# LoRaNow_v0.net
KiCad netlist of a schematic drawn in EAGLE
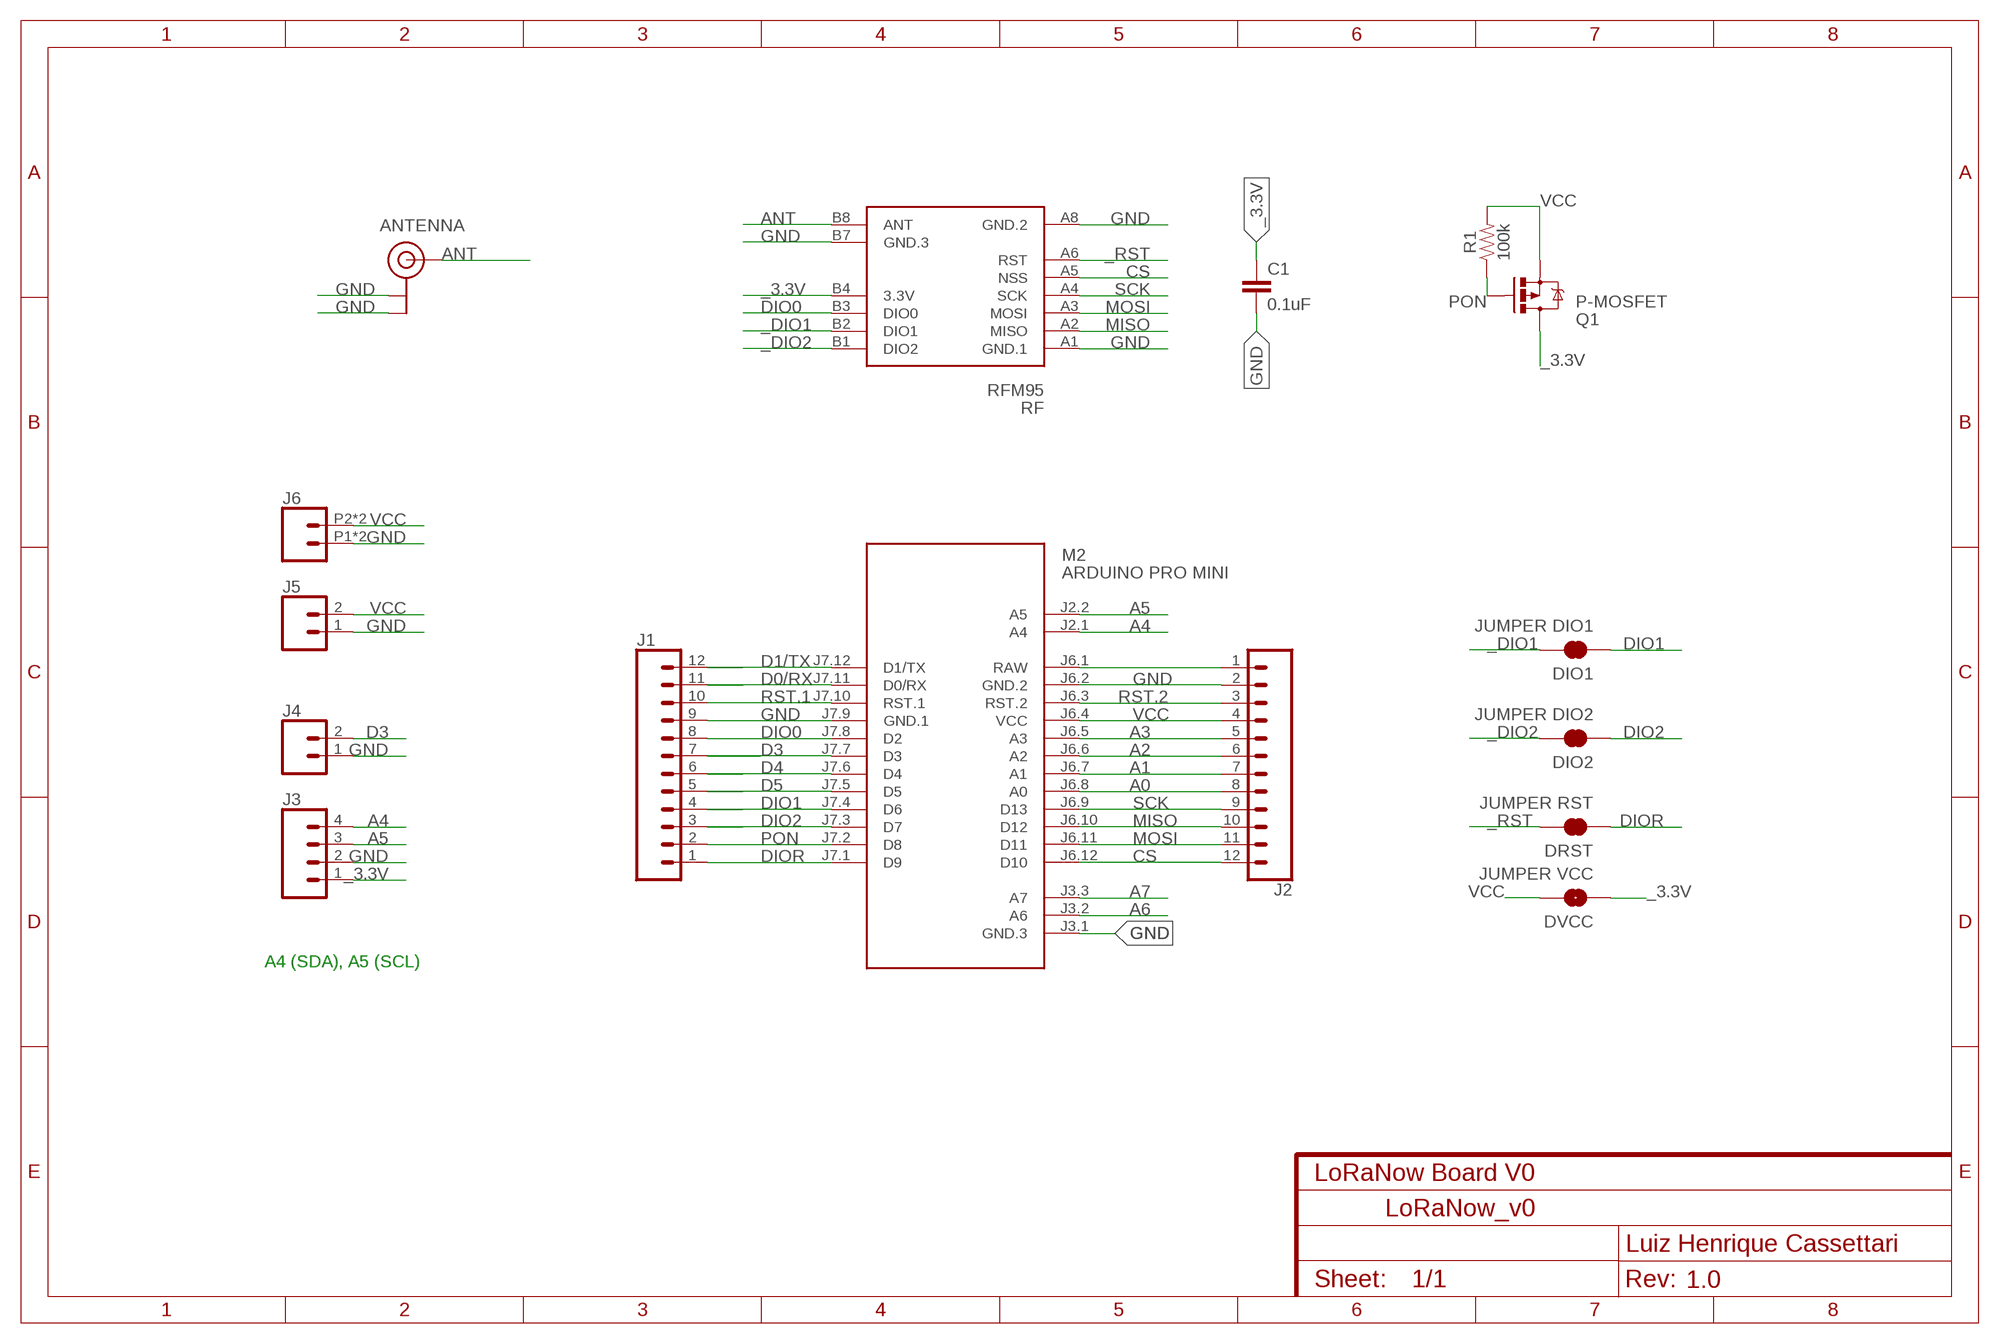
[diagram p0: schematic, sheet 1]

(export (version "E")
  (design (tool "Eeschema 10.0.6"))
  (components
    (comp (ref "ANTENNA")
      (value "U.FLU.FL2")
      (footprint "eagle-import:U.FL_2")
      (libsource (lib "eagle-import") (part "U.FLU.FL2"))
    )
    (comp (ref "C1")
      (value "0.1uF")
      (footprint "eagle-import:C0603K")
      (libsource (lib "eagle-import") (part "C-EUC0603K"))
    )
    (comp (ref "DIO1")
      (value "JUMPER DIO1")
      (footprint "eagle-import:SMT-JUMPER_2_NC_TRACE_NO-SILK")
      (libsource (lib "eagle-import") (part "JUMPER-SMT_2_NC_TRACE_NO-SILK"))
    )
    (comp (ref "DIO2")
      (value "JUMPER DIO2")
      (footprint "eagle-import:SMT-JUMPER_2_NC_TRACE_NO-SILK")
      (libsource (lib "eagle-import") (part "JUMPER-SMT_2_NC_TRACE_NO-SILK"))
    )
    (comp (ref "DRST")
      (value "JUMPER RST")
      (footprint "eagle-import:SMT-JUMPER_2_NC_TRACE_NO-SILK")
      (libsource (lib "eagle-import") (part "JUMPER-SMT_2_NC_TRACE_NO-SILK"))
    )
    (comp (ref "DVCC")
      (value "JUMPER VCC")
      (footprint "eagle-import:SMT-JUMPER_2_NO_NO-SILK")
      (libsource (lib "eagle-import") (part "JUMPER-SMT_2_NO_NO-SILK"))
    )
    (comp (ref "J1")
      (value "CONN_12NO_SILK")
      (footprint "eagle-import:1X12_NO_SILK")
      (libsource (lib "eagle-import") (part "CONN_12NO_SILK"))
    )
    (comp (ref "J2")
      (value "CONN_12NO_SILK")
      (footprint "eagle-import:1X12_NO_SILK")
      (libsource (lib "eagle-import") (part "CONN_12NO_SILK"))
    )
    (comp (ref "J3")
      (value "CONN_041X04_NO_SILK")
      (footprint "eagle-import:1X04_NO_SILK")
      (libsource (lib "eagle-import") (part "CONN_041X04_NO_SILK"))
    )
    (comp (ref "J4")
      (value "CONN_021X02_NO_SILK")
      (footprint "eagle-import:1X02_NO_SILK")
      (libsource (lib "eagle-import") (part "CONN_021X02_NO_SILK"))
    )
    (comp (ref "J5")
      (value "CONN_021X02_NO_SILK")
      (footprint "eagle-import:1X02_NO_SILK")
      (libsource (lib "eagle-import") (part "CONN_021X02_NO_SILK"))
    )
    (comp (ref "J6")
      (value "CONN_02SMALL_POKEHOME")
      (footprint "eagle-import:1X02_POKEHOME")
      (libsource (lib "eagle-import") (part "CONN_02SMALL_POKEHOME"))
    )
    (comp (ref "M2")
      (value "ARDUINO PRO MINI")
      (footprint "eagle-import:ARDUINO-PRO-MINI#NP#2")
      (libsource (lib "eagle-import") (part "ARDUINO-PRO-MINI-#NP2"))
    )
    (comp (ref "Q1")
      (value "P-MOSFET")
      (footprint "eagle-import:SOT23-3")
      (libsource (lib "eagle-import") (part "MOSFET-PCHANNELSMD"))
    )
    (comp (ref "R1")
      (value "100k")
      (footprint "eagle-import:0603")
      (libsource (lib "eagle-import") (part "100KOHM-0603-1/10W-1%"))
    )
    (comp (ref "RF")
      (value "RFM95")
      (footprint "eagle-import:WIRELESS-LORA-RFM95W#SMD#2")
      (libsource (lib "eagle-import") (part "WIRELESS-LORA-RFM95W-LORANOW"))
    )
  )
  (nets
    (net (code "1") (name "/A0") (class "Default")
      (node (ref "J2") (pin "8") (pinfunction "8_8") (pintype "passive"))
      (node (ref "M2") (pin "J6.8") (pinfunction "A0_J6.8") (pintype "bidirectional"))
    )
    (net (code "2") (name "/A1") (class "Default")
      (node (ref "J2") (pin "7") (pinfunction "7_7") (pintype "passive"))
      (node (ref "M2") (pin "J6.7") (pinfunction "A1_J6.7") (pintype "bidirectional"))
    )
    (net (code "3") (name "/A2") (class "Default")
      (node (ref "J2") (pin "6") (pinfunction "6_6") (pintype "passive"))
      (node (ref "M2") (pin "J6.6") (pinfunction "A2_J6.6") (pintype "bidirectional"))
    )
    (net (code "4") (name "/A3") (class "Default")
      (node (ref "J2") (pin "5") (pinfunction "5_5") (pintype "passive"))
      (node (ref "M2") (pin "J6.5") (pinfunction "A3_J6.5") (pintype "bidirectional"))
    )
    (net (code "5") (name "/A4") (class "Default")
      (node (ref "J3") (pin "4") (pinfunction "4_4") (pintype "passive"))
      (node (ref "M2") (pin "J2.1") (pinfunction "A4_J2.1") (pintype "bidirectional"))
    )
    (net (code "6") (name "/A5") (class "Default")
      (node (ref "J3") (pin "3") (pinfunction "3_3") (pintype "passive"))
      (node (ref "M2") (pin "J2.2") (pinfunction "A5_J2.2") (pintype "bidirectional"))
    )
    (net (code "7") (name "/A6") (class "Default")
      (node (ref "M2") (pin "J3.2") (pinfunction "A6_J3.2") (pintype "bidirectional"))
    )
    (net (code "8") (name "/A7") (class "Default")
      (node (ref "M2") (pin "J3.3") (pinfunction "A7_J3.3") (pintype "bidirectional"))
    )
    (net (code "9") (name "/ANT") (class "Default")
      (node (ref "ANTENNA") (pin "FEED") (pinfunction "SIGNAL_FEED") (pintype "bidirectional"))
      (node (ref "ANTENNA") (pin "FEED.P") (pinfunction "SIGNAL_FEED.P") (pintype "bidirectional"))
      (node (ref "RF") (pin "B8") (pinfunction "ANT_B8") (pintype "passive"))
    )
    (net (code "10") (name "/CS") (class "Default")
      (node (ref "J2") (pin "12") (pinfunction "12_12") (pintype "passive"))
      (node (ref "M2") (pin "J6.12") (pinfunction "D10_J6.12") (pintype "bidirectional"))
      (node (ref "RF") (pin "A5") (pinfunction "NSS_A5") (pintype "bidirectional"))
    )
    (net (code "11") (name "/D0{slash}RX") (class "Default")
      (node (ref "J1") (pin "11") (pinfunction "11_11") (pintype "passive"))
      (node (ref "M2") (pin "J7.11") (pinfunction "D0/RX_J7.11") (pintype "bidirectional"))
    )
    (net (code "12") (name "/D1{slash}TX") (class "Default")
      (node (ref "J1") (pin "12") (pinfunction "12_12") (pintype "passive"))
      (node (ref "M2") (pin "J7.12") (pinfunction "D1/TX_J7.12") (pintype "bidirectional"))
    )
    (net (code "13") (name "/D3") (class "Default")
      (node (ref "J1") (pin "7") (pinfunction "7_7") (pintype "passive"))
      (node (ref "J4") (pin "2") (pinfunction "2_2") (pintype "passive"))
      (node (ref "M2") (pin "J7.7") (pinfunction "D3_J7.7") (pintype "bidirectional"))
    )
    (net (code "14") (name "/D4") (class "Default")
      (node (ref "J1") (pin "6") (pinfunction "6_6") (pintype "passive"))
      (node (ref "M2") (pin "J7.6") (pinfunction "D4_J7.6") (pintype "bidirectional"))
    )
    (net (code "15") (name "/D5") (class "Default")
      (node (ref "J1") (pin "5") (pinfunction "5_5") (pintype "passive"))
      (node (ref "M2") (pin "J7.5") (pinfunction "D5_J7.5") (pintype "bidirectional"))
    )
    (net (code "16") (name "/DIO0") (class "Default")
      (node (ref "J1") (pin "8") (pinfunction "8_8") (pintype "passive"))
      (node (ref "M2") (pin "J7.8") (pinfunction "D2_J7.8") (pintype "bidirectional"))
      (node (ref "RF") (pin "B3") (pinfunction "DIO0_B3") (pintype "bidirectional"))
    )
    (net (code "17") (name "/DIO1") (class "Default")
      (node (ref "DIO1") (pin "1") (pinfunction "1_1") (pintype "passive"))
      (node (ref "J1") (pin "4") (pinfunction "4_4") (pintype "passive"))
      (node (ref "M2") (pin "J7.4") (pinfunction "D6_J7.4") (pintype "bidirectional"))
    )
    (net (code "18") (name "/DIO2") (class "Default")
      (node (ref "DIO2") (pin "1") (pinfunction "1_1") (pintype "passive"))
      (node (ref "J1") (pin "3") (pinfunction "3_3") (pintype "passive"))
      (node (ref "M2") (pin "J7.3") (pinfunction "D7_J7.3") (pintype "bidirectional"))
    )
    (net (code "19") (name "/DIOR") (class "Default")
      (node (ref "DRST") (pin "1") (pinfunction "1_1") (pintype "passive"))
      (node (ref "J1") (pin "1") (pinfunction "1_1") (pintype "passive"))
      (node (ref "M2") (pin "J7.1") (pinfunction "D9_J7.1") (pintype "bidirectional"))
    )
    (net (code "20") (name "/MISO") (class "Default")
      (node (ref "J2") (pin "10") (pinfunction "10_10") (pintype "passive"))
      (node (ref "M2") (pin "J6.10") (pinfunction "D12_J6.10") (pintype "bidirectional"))
      (node (ref "RF") (pin "A2") (pinfunction "MISO_A2") (pintype "bidirectional"))
    )
    (net (code "21") (name "/MOSI") (class "Default")
      (node (ref "J2") (pin "11") (pinfunction "11_11") (pintype "passive"))
      (node (ref "M2") (pin "J6.11") (pinfunction "D11_J6.11") (pintype "bidirectional"))
      (node (ref "RF") (pin "A3") (pinfunction "MOSI_A3") (pintype "bidirectional"))
    )
    (net (code "22") (name "/PON") (class "Default")
      (node (ref "J1") (pin "2") (pinfunction "2_2") (pintype "passive"))
      (node (ref "M2") (pin "J7.2") (pinfunction "D8_J7.2") (pintype "bidirectional"))
      (node (ref "Q1") (pin "1") (pinfunction "G_1") (pintype "passive"))
      (node (ref "R1") (pin "1") (pinfunction "1_1") (pintype "passive"))
    )
    (net (code "23") (name "/RST.1") (class "Default")
      (node (ref "J1") (pin "10") (pinfunction "10_10") (pintype "passive"))
      (node (ref "M2") (pin "J7.10") (pinfunction "RST.1_J7.10") (pintype "bidirectional"))
    )
    (net (code "24") (name "/RST.2") (class "Default")
      (node (ref "J2") (pin "3") (pinfunction "3_3") (pintype "passive"))
      (node (ref "M2") (pin "J6.3") (pinfunction "RST.2_J6.3") (pintype "bidirectional"))
    )
    (net (code "25") (name "/SCK") (class "Default")
      (node (ref "J2") (pin "9") (pinfunction "9_9") (pintype "passive"))
      (node (ref "M2") (pin "J6.9") (pinfunction "D13_J6.9") (pintype "bidirectional"))
      (node (ref "RF") (pin "A4") (pinfunction "SCK_A4") (pintype "bidirectional"))
    )
    (net (code "26") (name "/VCC") (class "Default")
      (node (ref "DVCC") (pin "2") (pinfunction "2_2") (pintype "passive"))
      (node (ref "J2") (pin "4") (pinfunction "4_4") (pintype "passive"))
      (node (ref "J5") (pin "2") (pinfunction "2_2") (pintype "passive"))
      (node (ref "J6") (pin "P2") (pinfunction "2_P2") (pintype "passive"))
      (node (ref "J6") (pin "P4") (pinfunction "2_P4") (pintype "passive"))
      (node (ref "M2") (pin "J6.4") (pinfunction "VCC_J6.4") (pintype "power_in"))
      (node (ref "Q1") (pin "2") (pinfunction "S_2") (pintype "passive"))
      (node (ref "R1") (pin "2") (pinfunction "2_2") (pintype "passive"))
    )
    (net (code "27") (name "/_DIO1") (class "Default")
      (node (ref "DIO1") (pin "2") (pinfunction "2_2") (pintype "passive"))
      (node (ref "RF") (pin "B2") (pinfunction "DIO1_B2") (pintype "bidirectional"))
    )
    (net (code "28") (name "/_DIO2") (class "Default")
      (node (ref "DIO2") (pin "2") (pinfunction "2_2") (pintype "passive"))
      (node (ref "RF") (pin "B1") (pinfunction "DIO2_B1") (pintype "bidirectional"))
    )
    (net (code "29") (name "/_RST") (class "Default")
      (node (ref "DRST") (pin "2") (pinfunction "2_2") (pintype "passive"))
      (node (ref "RF") (pin "A6") (pinfunction "RST_A6") (pintype "bidirectional"))
    )
    (net (code "30") (name "GND") (class "Default")
      (node (ref "ANTENNA") (pin "1") (pinfunction "GND_1") (pintype "bidirectional"))
      (node (ref "ANTENNA") (pin "2") (pinfunction "GND_2") (pintype "bidirectional"))
      (node (ref "ANTENNA") (pin "3") (pinfunction "GND_3") (pintype "bidirectional"))
      (node (ref "ANTENNA") (pin "4") (pinfunction "GND_4") (pintype "bidirectional"))
      (node (ref "ANTENNA") (pin "5") (pinfunction "GND_5") (pintype "bidirectional"))
      (node (ref "ANTENNA") (pin "6") (pinfunction "GND_6") (pintype "bidirectional"))
      (node (ref "C1") (pin "2") (pinfunction "2_2") (pintype "passive"))
      (node (ref "J1") (pin "9") (pinfunction "9_9") (pintype "passive"))
      (node (ref "J2") (pin "2") (pinfunction "2_2") (pintype "passive"))
      (node (ref "J3") (pin "2") (pinfunction "2_2") (pintype "passive"))
      (node (ref "J4") (pin "1") (pinfunction "1_1") (pintype "passive"))
      (node (ref "J5") (pin "1") (pinfunction "1_1") (pintype "passive"))
      (node (ref "J6") (pin "P1") (pinfunction "1_P1") (pintype "passive"))
      (node (ref "J6") (pin "P3") (pinfunction "1_P3") (pintype "passive"))
      (node (ref "M2") (pin "J3.1") (pinfunction "GND.3_J3.1") (pintype "bidirectional"))
      (node (ref "M2") (pin "J6.2") (pinfunction "GND.2_J6.2") (pintype "power_in"))
      (node (ref "M2") (pin "J7.9") (pinfunction "GND.1_J7.9") (pintype "power_in"))
      (node (ref "RF") (pin "A1") (pinfunction "GND.1_A1") (pintype "power_in"))
      (node (ref "RF") (pin "A8") (pinfunction "GND.2_A8") (pintype "power_in"))
      (node (ref "RF") (pin "B7") (pinfunction "GND.3_B7") (pintype "power_in"))
    )
    (net (code "31") (name "Net-(M2-RAW)") (class "Default")
      (node (ref "J2") (pin "1") (pinfunction "1_1") (pintype "passive"))
      (node (ref "M2") (pin "J6.1") (pinfunction "RAW_J6.1") (pintype "power_in"))
    )
    (net (code "32") (name "_3.3V") (class "Default")
      (node (ref "C1") (pin "1") (pinfunction "1_1") (pintype "passive"))
      (node (ref "DVCC") (pin "1") (pinfunction "1_1") (pintype "passive"))
      (node (ref "J3") (pin "1") (pinfunction "1_1") (pintype "passive"))
      (node (ref "Q1") (pin "3") (pinfunction "D_3") (pintype "passive"))
      (node (ref "RF") (pin "B4") (pinfunction "3.3V_B4") (pintype "power_in"))
    )
  )
)
